# Youssef_DHRIF.net
KiCad netlist of a schematic drawn in EAGLE
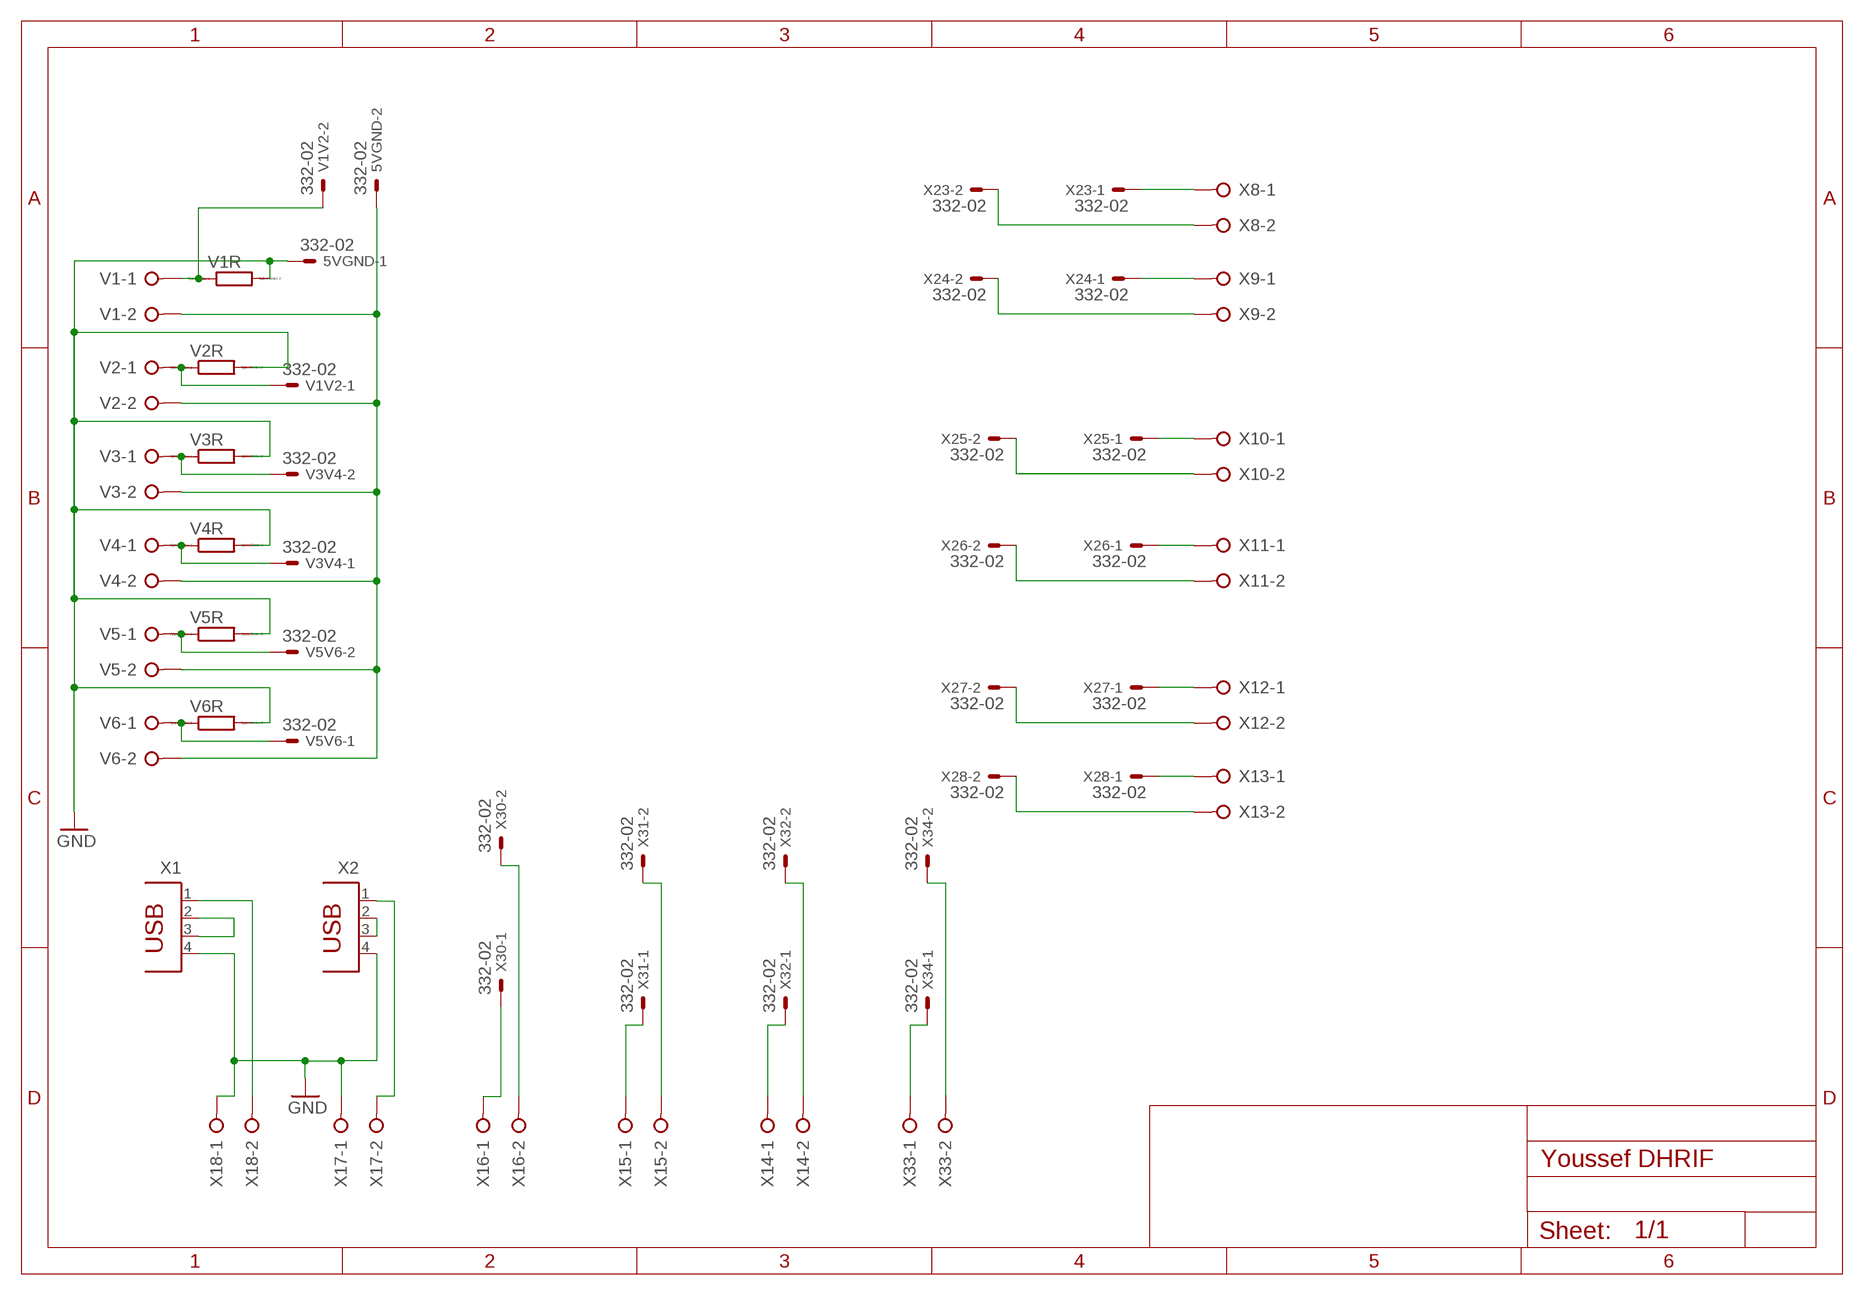
[diagram p0: schematic, sheet 1]

(export (version "E")
  (design (tool "Eeschema 10.0.6"))
  (components
    (comp (ref "5VGND")
      (value "332-02")
      (footprint "eagle-import:332-02")
      (libsource (lib "eagle-import") (part "332-02"))
    )
    (comp (ref "V1")
      (value "W237-02P")
      (footprint "eagle-import:W237-132")
      (libsource (lib "eagle-import") (part "W237-02P"))
    )
    (comp (ref "V1R")
      (value "R0207/10")
      (footprint "eagle-import:0207_10")
      (libsource (lib "eagle-import") (part "R0207/10"))
    )
    (comp (ref "V1V2")
      (value "332-02")
      (footprint "eagle-import:332-02")
      (libsource (lib "eagle-import") (part "332-02"))
    )
    (comp (ref "V2")
      (value "W237-02P")
      (footprint "eagle-import:W237-132")
      (libsource (lib "eagle-import") (part "W237-02P"))
    )
    (comp (ref "V2R")
      (value "R0207/10")
      (footprint "eagle-import:0207_10")
      (libsource (lib "eagle-import") (part "R0207/10"))
    )
    (comp (ref "V3")
      (value "W237-02P")
      (footprint "eagle-import:W237-132")
      (libsource (lib "eagle-import") (part "W237-02P"))
    )
    (comp (ref "V3R")
      (value "R0207/10")
      (footprint "eagle-import:0207_10")
      (libsource (lib "eagle-import") (part "R0207/10"))
    )
    (comp (ref "V3V4")
      (value "332-02")
      (footprint "eagle-import:332-02")
      (libsource (lib "eagle-import") (part "332-02"))
    )
    (comp (ref "V4")
      (value "W237-02P")
      (footprint "eagle-import:W237-132")
      (libsource (lib "eagle-import") (part "W237-02P"))
    )
    (comp (ref "V4R")
      (value "R0207/10")
      (footprint "eagle-import:0207_10")
      (libsource (lib "eagle-import") (part "R0207/10"))
    )
    (comp (ref "V5")
      (value "W237-02P")
      (footprint "eagle-import:W237-132")
      (libsource (lib "eagle-import") (part "W237-02P"))
    )
    (comp (ref "V5R")
      (value "R0207/10")
      (footprint "eagle-import:0207_10")
      (libsource (lib "eagle-import") (part "R0207/10"))
    )
    (comp (ref "V5V6")
      (value "332-02")
      (footprint "eagle-import:332-02")
      (libsource (lib "eagle-import") (part "332-02"))
    )
    (comp (ref "V6")
      (value "W237-02P")
      (footprint "eagle-import:W237-132")
      (libsource (lib "eagle-import") (part "W237-02P"))
    )
    (comp (ref "V6R")
      (value "R0207/10")
      (footprint "eagle-import:0207_10")
      (libsource (lib "eagle-import") (part "R0207/10"))
    )
    (comp (ref "X1")
      (value "PN87520")
      (footprint "eagle-import:PN87520")
      (libsource (lib "eagle-import") (part "PN87520"))
    )
    (comp (ref "X2")
      (value "PN87520")
      (footprint "eagle-import:PN87520")
      (libsource (lib "eagle-import") (part "PN87520"))
    )
    (comp (ref "X8")
      (value "W237-02P")
      (footprint "eagle-import:W237-132")
      (libsource (lib "eagle-import") (part "W237-02P"))
    )
    (comp (ref "X9")
      (value "W237-02P")
      (footprint "eagle-import:W237-132")
      (libsource (lib "eagle-import") (part "W237-02P"))
    )
    (comp (ref "X10")
      (value "W237-02P")
      (footprint "eagle-import:W237-132")
      (libsource (lib "eagle-import") (part "W237-02P"))
    )
    (comp (ref "X11")
      (value "W237-02P")
      (footprint "eagle-import:W237-132")
      (libsource (lib "eagle-import") (part "W237-02P"))
    )
    (comp (ref "X12")
      (value "W237-02P")
      (footprint "eagle-import:W237-132")
      (libsource (lib "eagle-import") (part "W237-02P"))
    )
    (comp (ref "X13")
      (value "W237-02P")
      (footprint "eagle-import:W237-132")
      (libsource (lib "eagle-import") (part "W237-02P"))
    )
    (comp (ref "X14")
      (value "W237-02P")
      (footprint "eagle-import:W237-132")
      (libsource (lib "eagle-import") (part "W237-02P"))
    )
    (comp (ref "X15")
      (value "W237-02P")
      (footprint "eagle-import:W237-132")
      (libsource (lib "eagle-import") (part "W237-02P"))
    )
    (comp (ref "X16")
      (value "W237-02P")
      (footprint "eagle-import:W237-132")
      (libsource (lib "eagle-import") (part "W237-02P"))
    )
    (comp (ref "X17")
      (value "W237-02P")
      (footprint "eagle-import:W237-132")
      (libsource (lib "eagle-import") (part "W237-02P"))
    )
    (comp (ref "X18")
      (value "W237-02P")
      (footprint "eagle-import:W237-132")
      (libsource (lib "eagle-import") (part "W237-02P"))
    )
    (comp (ref "X23")
      (value "332-02")
      (footprint "eagle-import:332-02")
      (libsource (lib "eagle-import") (part "332-02"))
    )
    (comp (ref "X24")
      (value "332-02")
      (footprint "eagle-import:332-02")
      (libsource (lib "eagle-import") (part "332-02"))
    )
    (comp (ref "X25")
      (value "332-02")
      (footprint "eagle-import:332-02")
      (libsource (lib "eagle-import") (part "332-02"))
    )
    (comp (ref "X26")
      (value "332-02")
      (footprint "eagle-import:332-02")
      (libsource (lib "eagle-import") (part "332-02"))
    )
    (comp (ref "X27")
      (value "332-02")
      (footprint "eagle-import:332-02")
      (libsource (lib "eagle-import") (part "332-02"))
    )
    (comp (ref "X28")
      (value "332-02")
      (footprint "eagle-import:332-02")
      (libsource (lib "eagle-import") (part "332-02"))
    )
    (comp (ref "X30")
      (value "332-02")
      (footprint "eagle-import:332-02")
      (libsource (lib "eagle-import") (part "332-02"))
    )
    (comp (ref "X31")
      (value "332-02")
      (footprint "eagle-import:332-02")
      (libsource (lib "eagle-import") (part "332-02"))
    )
    (comp (ref "X32")
      (value "332-02")
      (footprint "eagle-import:332-02")
      (libsource (lib "eagle-import") (part "332-02"))
    )
    (comp (ref "X33")
      (value "W237-02P")
      (footprint "eagle-import:W237-132")
      (libsource (lib "eagle-import") (part "W237-02P"))
    )
    (comp (ref "X34")
      (value "332-02")
      (footprint "eagle-import:332-02")
      (libsource (lib "eagle-import") (part "332-02"))
    )
  )
  (nets
    (net (code "1") (name "GND") (class "Default")
      (node (ref "5VGND") (pin "1") (pinfunction "S_1") (pintype "passive"))
      (node (ref "V1R") (pin "2") (pinfunction "2_2") (pintype "passive"))
      (node (ref "V2R") (pin "2") (pinfunction "2_2") (pintype "passive"))
      (node (ref "V3R") (pin "2") (pinfunction "2_2") (pintype "passive"))
      (node (ref "V4R") (pin "2") (pinfunction "2_2") (pintype "passive"))
      (node (ref "V5R") (pin "2") (pinfunction "2_2") (pintype "passive"))
      (node (ref "V6R") (pin "2") (pinfunction "2_2") (pintype "passive"))
      (node (ref "X1") (pin "4") (pinfunction "4_4") (pintype "passive"))
      (node (ref "X17") (pin "1") (pinfunction "KL_1") (pintype "passive"))
      (node (ref "X18") (pin "1") (pinfunction "KL_1") (pintype "passive"))
      (node (ref "X2") (pin "4") (pinfunction "4_4") (pintype "passive"))
    )
    (net (code "2") (name "Net-(5VGNDB-S)") (class "Default")
      (node (ref "5VGND") (pin "2") (pinfunction "S_2") (pintype "passive"))
      (node (ref "V1") (pin "2") (pinfunction "KL_2") (pintype "passive"))
      (node (ref "V2") (pin "2") (pinfunction "KL_2") (pintype "passive"))
      (node (ref "V3") (pin "2") (pinfunction "KL_2") (pintype "passive"))
      (node (ref "V4") (pin "2") (pinfunction "KL_2") (pintype "passive"))
      (node (ref "V5") (pin "2") (pinfunction "KL_2") (pintype "passive"))
      (node (ref "V6") (pin "2") (pinfunction "KL_2") (pintype "passive"))
    )
    (net (code "3") (name "Net-(V1A-KL)") (class "Default")
      (node (ref "V1") (pin "1") (pinfunction "KL_1") (pintype "passive"))
      (node (ref "V1R") (pin "1") (pinfunction "1_1") (pintype "passive"))
      (node (ref "V1V2") (pin "2") (pinfunction "S_2") (pintype "passive"))
    )
    (net (code "4") (name "Net-(V1V2A-S)") (class "Default")
      (node (ref "V1V2") (pin "1") (pinfunction "S_1") (pintype "passive"))
      (node (ref "V2") (pin "1") (pinfunction "KL_1") (pintype "passive"))
      (node (ref "V2R") (pin "1") (pinfunction "1_1") (pintype "passive"))
    )
    (net (code "5") (name "Net-(V3A-KL)") (class "Default")
      (node (ref "V3") (pin "1") (pinfunction "KL_1") (pintype "passive"))
      (node (ref "V3R") (pin "1") (pinfunction "1_1") (pintype "passive"))
      (node (ref "V3V4") (pin "2") (pinfunction "S_2") (pintype "passive"))
    )
    (net (code "6") (name "Net-(V3V4A-S)") (class "Default")
      (node (ref "V3V4") (pin "1") (pinfunction "S_1") (pintype "passive"))
      (node (ref "V4") (pin "1") (pinfunction "KL_1") (pintype "passive"))
      (node (ref "V4R") (pin "1") (pinfunction "1_1") (pintype "passive"))
    )
    (net (code "7") (name "Net-(V5A-KL)") (class "Default")
      (node (ref "V5") (pin "1") (pinfunction "KL_1") (pintype "passive"))
      (node (ref "V5R") (pin "1") (pinfunction "1_1") (pintype "passive"))
      (node (ref "V5V6") (pin "2") (pinfunction "S_2") (pintype "passive"))
    )
    (net (code "8") (name "Net-(V5V6A-S)") (class "Default")
      (node (ref "V5V6") (pin "1") (pinfunction "S_1") (pintype "passive"))
      (node (ref "V6") (pin "1") (pinfunction "KL_1") (pintype "passive"))
      (node (ref "V6R") (pin "1") (pinfunction "1_1") (pintype "passive"))
    )
    (net (code "9") (name "Net-(X1-Pad2)") (class "Default")
      (node (ref "X1") (pin "2") (pinfunction "2_2") (pintype "passive"))
      (node (ref "X1") (pin "3") (pinfunction "3_3") (pintype "passive"))
    )
    (net (code "10") (name "Net-(X2-Pad2)") (class "Default")
      (node (ref "X2") (pin "2") (pinfunction "2_2") (pintype "passive"))
      (node (ref "X2") (pin "3") (pinfunction "3_3") (pintype "passive"))
    )
    (net (code "11") (name "Net-(X10A-KL)") (class "Default")
      (node (ref "X10") (pin "1") (pinfunction "KL_1") (pintype "passive"))
      (node (ref "X25") (pin "1") (pinfunction "S_1") (pintype "passive"))
    )
    (net (code "12") (name "Net-(X10B-KL)") (class "Default")
      (node (ref "X10") (pin "2") (pinfunction "KL_2") (pintype "passive"))
      (node (ref "X25") (pin "2") (pinfunction "S_2") (pintype "passive"))
    )
    (net (code "13") (name "Net-(X11A-KL)") (class "Default")
      (node (ref "X11") (pin "1") (pinfunction "KL_1") (pintype "passive"))
      (node (ref "X26") (pin "1") (pinfunction "S_1") (pintype "passive"))
    )
    (net (code "14") (name "Net-(X11B-KL)") (class "Default")
      (node (ref "X11") (pin "2") (pinfunction "KL_2") (pintype "passive"))
      (node (ref "X26") (pin "2") (pinfunction "S_2") (pintype "passive"))
    )
    (net (code "15") (name "Net-(X12A-KL)") (class "Default")
      (node (ref "X12") (pin "1") (pinfunction "KL_1") (pintype "passive"))
      (node (ref "X27") (pin "1") (pinfunction "S_1") (pintype "passive"))
    )
    (net (code "16") (name "Net-(X12B-KL)") (class "Default")
      (node (ref "X12") (pin "2") (pinfunction "KL_2") (pintype "passive"))
      (node (ref "X27") (pin "2") (pinfunction "S_2") (pintype "passive"))
    )
    (net (code "17") (name "Net-(X13A-KL)") (class "Default")
      (node (ref "X13") (pin "1") (pinfunction "KL_1") (pintype "passive"))
      (node (ref "X28") (pin "1") (pinfunction "S_1") (pintype "passive"))
    )
    (net (code "18") (name "Net-(X13B-KL)") (class "Default")
      (node (ref "X13") (pin "2") (pinfunction "KL_2") (pintype "passive"))
      (node (ref "X28") (pin "2") (pinfunction "S_2") (pintype "passive"))
    )
    (net (code "19") (name "Net-(X14A-KL)") (class "Default")
      (node (ref "X14") (pin "1") (pinfunction "KL_1") (pintype "passive"))
      (node (ref "X32") (pin "1") (pinfunction "S_1") (pintype "passive"))
    )
    (net (code "20") (name "Net-(X14B-KL)") (class "Default")
      (node (ref "X14") (pin "2") (pinfunction "KL_2") (pintype "passive"))
      (node (ref "X32") (pin "2") (pinfunction "S_2") (pintype "passive"))
    )
    (net (code "21") (name "Net-(X15A-KL)") (class "Default")
      (node (ref "X15") (pin "1") (pinfunction "KL_1") (pintype "passive"))
      (node (ref "X31") (pin "1") (pinfunction "S_1") (pintype "passive"))
    )
    (net (code "22") (name "Net-(X15B-KL)") (class "Default")
      (node (ref "X15") (pin "2") (pinfunction "KL_2") (pintype "passive"))
      (node (ref "X31") (pin "2") (pinfunction "S_2") (pintype "passive"))
    )
    (net (code "23") (name "Net-(X16A-KL)") (class "Default")
      (node (ref "X16") (pin "1") (pinfunction "KL_1") (pintype "passive"))
      (node (ref "X30") (pin "1") (pinfunction "S_1") (pintype "passive"))
    )
    (net (code "24") (name "Net-(X16B-KL)") (class "Default")
      (node (ref "X16") (pin "2") (pinfunction "KL_2") (pintype "passive"))
      (node (ref "X30") (pin "2") (pinfunction "S_2") (pintype "passive"))
    )
    (net (code "25") (name "Net-(X17B-KL)") (class "Default")
      (node (ref "X17") (pin "2") (pinfunction "KL_2") (pintype "passive"))
      (node (ref "X2") (pin "1") (pinfunction "1_1") (pintype "passive"))
    )
    (net (code "26") (name "Net-(X18B-KL)") (class "Default")
      (node (ref "X1") (pin "1") (pinfunction "1_1") (pintype "passive"))
      (node (ref "X18") (pin "2") (pinfunction "KL_2") (pintype "passive"))
    )
    (net (code "27") (name "Net-(X23A-S)") (class "Default")
      (node (ref "X23") (pin "1") (pinfunction "S_1") (pintype "passive"))
      (node (ref "X8") (pin "1") (pinfunction "KL_1") (pintype "passive"))
    )
    (net (code "28") (name "Net-(X23B-S)") (class "Default")
      (node (ref "X23") (pin "2") (pinfunction "S_2") (pintype "passive"))
      (node (ref "X8") (pin "2") (pinfunction "KL_2") (pintype "passive"))
    )
    (net (code "29") (name "Net-(X24A-S)") (class "Default")
      (node (ref "X24") (pin "1") (pinfunction "S_1") (pintype "passive"))
      (node (ref "X9") (pin "1") (pinfunction "KL_1") (pintype "passive"))
    )
    (net (code "30") (name "Net-(X24B-S)") (class "Default")
      (node (ref "X24") (pin "2") (pinfunction "S_2") (pintype "passive"))
      (node (ref "X9") (pin "2") (pinfunction "KL_2") (pintype "passive"))
    )
    (net (code "31") (name "Net-(X33A-KL)") (class "Default")
      (node (ref "X33") (pin "1") (pinfunction "KL_1") (pintype "passive"))
      (node (ref "X34") (pin "1") (pinfunction "S_1") (pintype "passive"))
    )
    (net (code "32") (name "Net-(X33B-KL)") (class "Default")
      (node (ref "X33") (pin "2") (pinfunction "KL_2") (pintype "passive"))
      (node (ref "X34") (pin "2") (pinfunction "S_2") (pintype "passive"))
    )
  )
)
